# 4_valve_front_connect.net
KiCad netlist of a schematic drawn in EAGLE
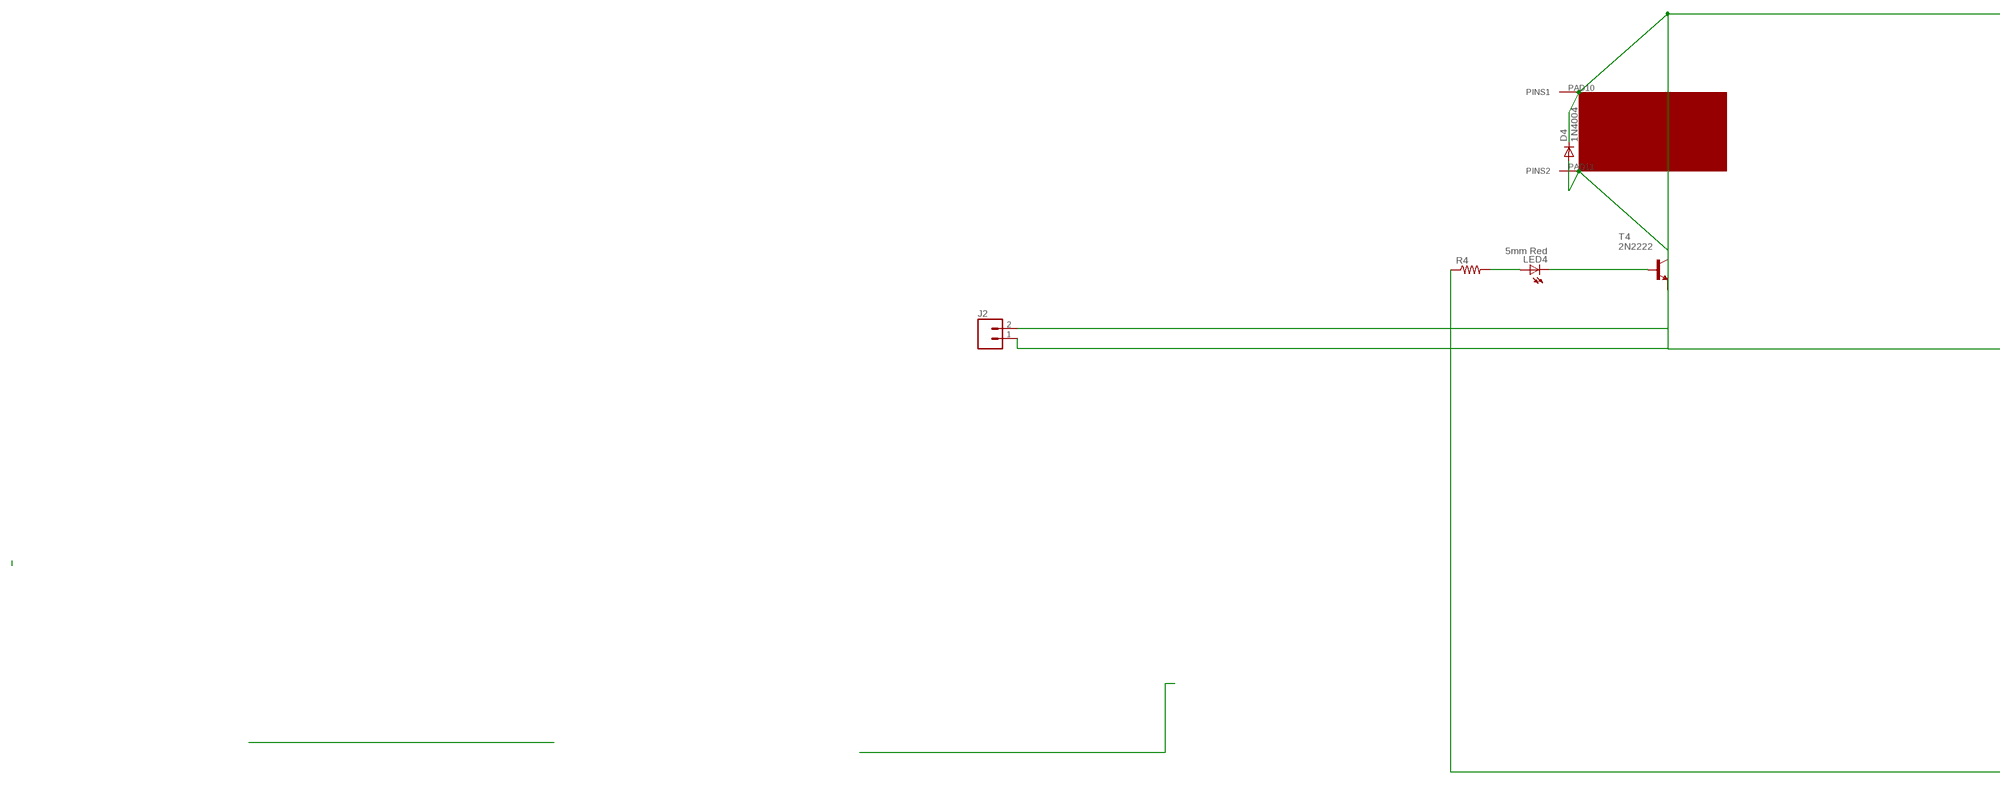
[diagram p0: schematic, sheet 1, part 1 of 2]
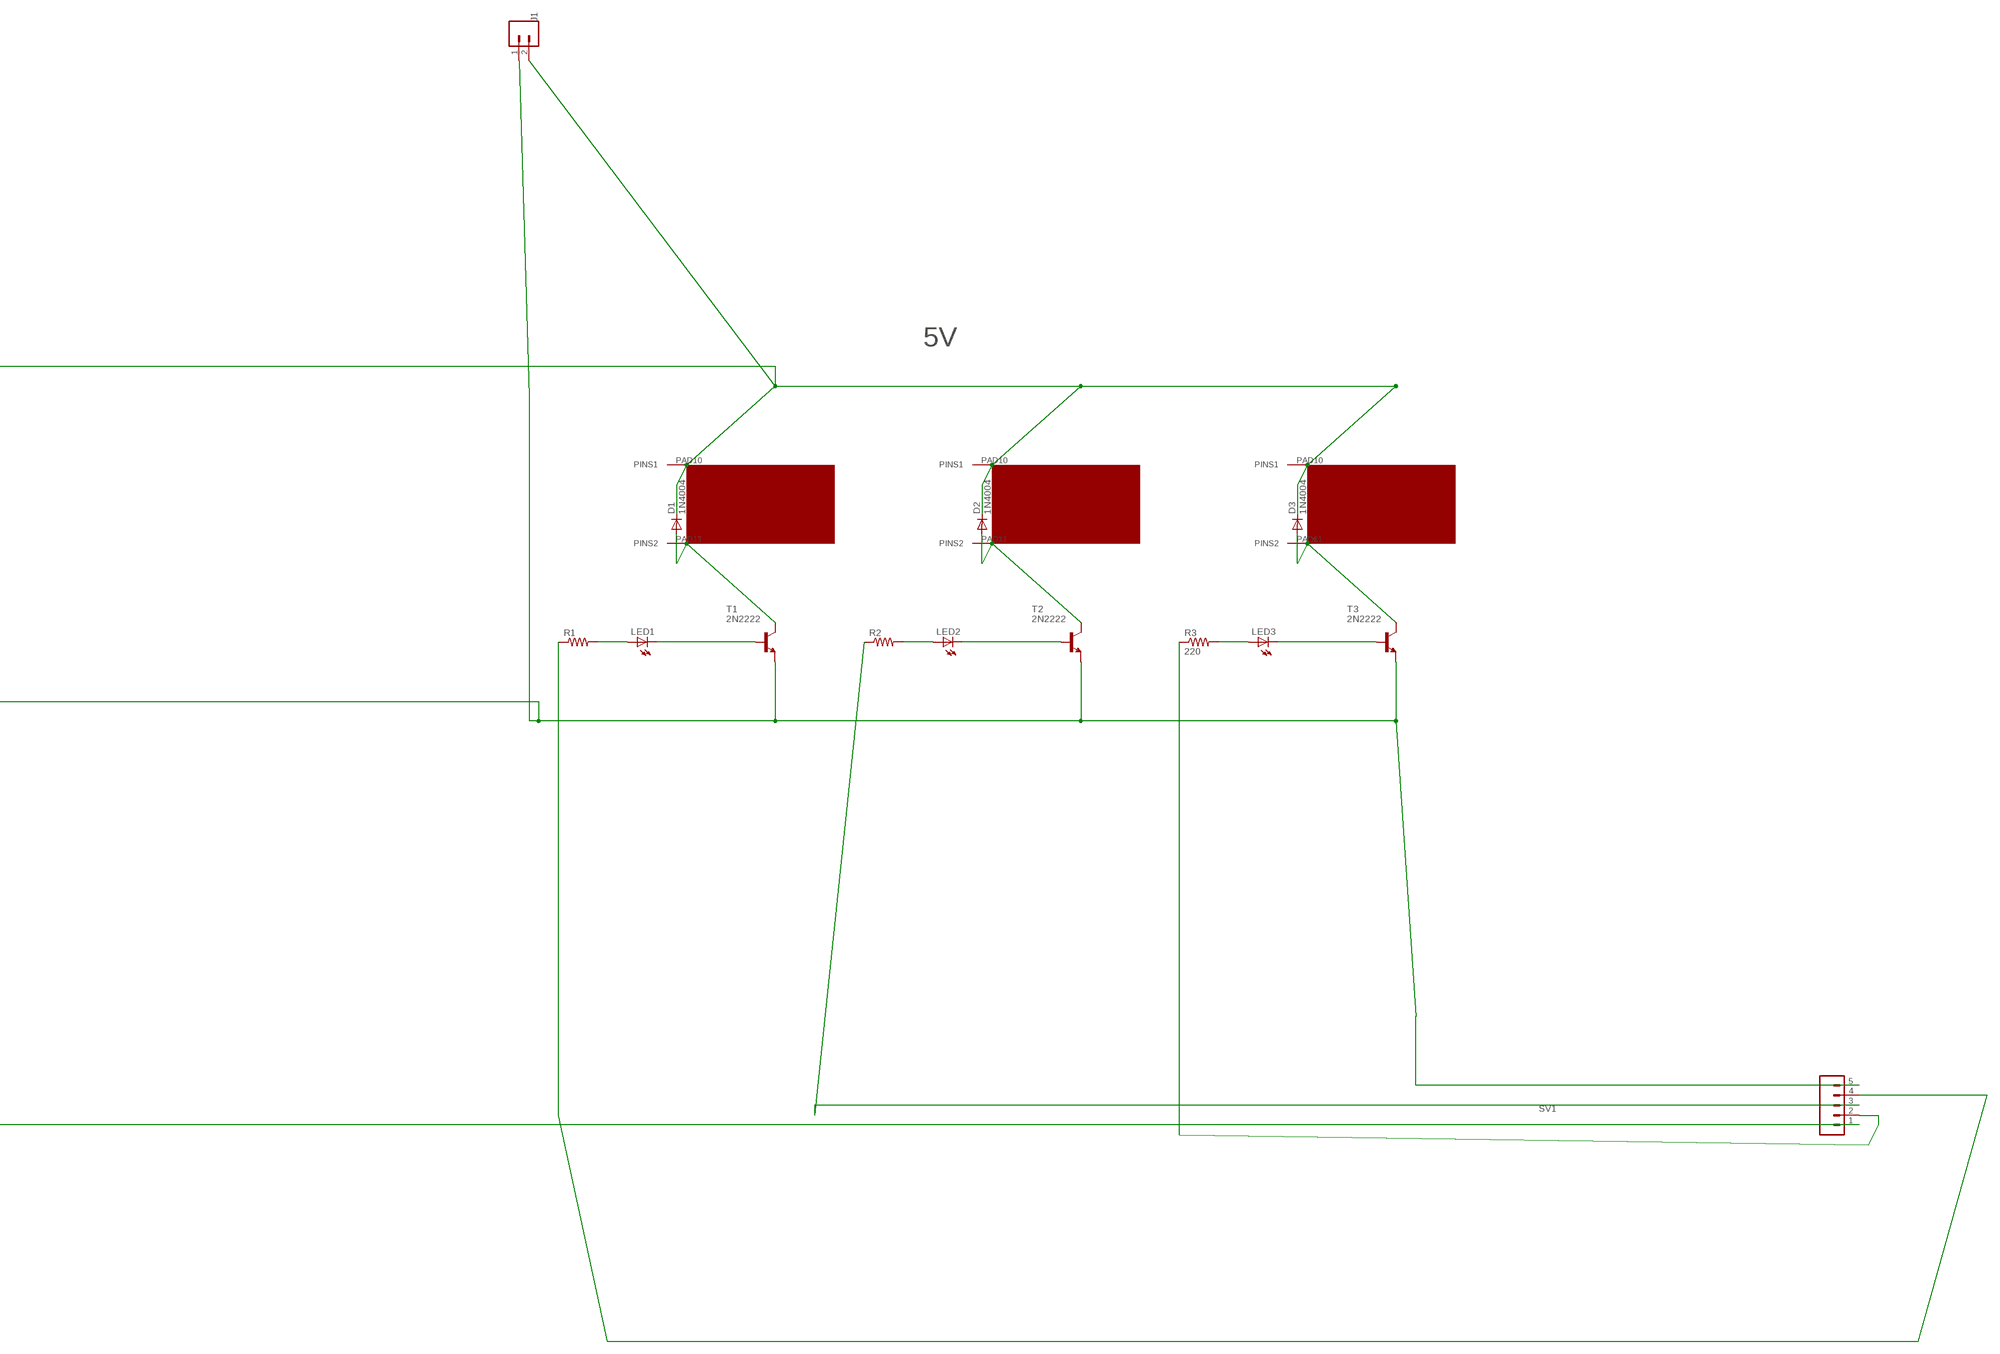
[diagram p1: schematic, sheet 1, part 2 of 2]

(export (version "E")
  (design (tool "Eeschema 10.0.6"))
  (components
    (comp (ref "D1")
      (value "1N4004")
      (footprint "eagle-import:DO41-10")
      (libsource (lib "eagle-import") (part "1N4004"))
    )
    (comp (ref "D2")
      (value "1N4004")
      (footprint "eagle-import:DO41-10")
      (libsource (lib "eagle-import") (part "1N4004"))
    )
    (comp (ref "D3")
      (value "1N4004")
      (footprint "eagle-import:DO41-10")
      (libsource (lib "eagle-import") (part "1N4004"))
    )
    (comp (ref "D4")
      (value "1N4004")
      (footprint "eagle-import:DO41-10")
      (libsource (lib "eagle-import") (part "1N4004"))
    )
    (comp (ref "J1")
      (value "CONN_023.5MM")
      (footprint "eagle-import:SCREWTERMINAL-3.5MM-2")
      (libsource (lib "eagle-import") (part "CONN_023.5MM"))
    )
    (comp (ref "J2")
      (value "CONN_02")
      (footprint "eagle-import:1X02")
      (libsource (lib "eagle-import") (part "CONN_02"))
    )
    (comp (ref "LED1")
      (value "LED5MM")
      (footprint "eagle-import:LED5MM")
      (libsource (lib "eagle-import") (part "LED5MM"))
    )
    (comp (ref "LED2")
      (value "LED5MM")
      (footprint "eagle-import:LED5MM")
      (libsource (lib "eagle-import") (part "LED5MM"))
    )
    (comp (ref "LED3")
      (value "LED5MM")
      (footprint "eagle-import:LED5MM")
      (libsource (lib "eagle-import") (part "LED5MM"))
    )
    (comp (ref "LED4")
      (value "5mm Red")
      (footprint "eagle-import:LED5MM")
      (libsource (lib "eagle-import") (part "LED5MM"))
    )
    (comp (ref "R1")
      (value "R-US_0207/10")
      (footprint "eagle-import:0207_10")
      (libsource (lib "eagle-import") (part "R-US_0207/10"))
    )
    (comp (ref "R2")
      (value "R-US_0207/10")
      (footprint "eagle-import:0207_10")
      (libsource (lib "eagle-import") (part "R-US_0207/10"))
    )
    (comp (ref "R3")
      (value "220")
      (footprint "eagle-import:0207_10")
      (libsource (lib "eagle-import") (part "R-US_0207/10"))
    )
    (comp (ref "R4")
      (value "R-US_0207/10")
      (footprint "eagle-import:0207_10")
      (libsource (lib "eagle-import") (part "R-US_0207/10"))
    )
    (comp (ref "SV1")
      (value "CONN_05")
      (footprint "eagle-import:1X05")
      (libsource (lib "eagle-import") (part "CONN_05"))
    )
    (comp (ref "T1")
      (value "2N2222")
      (footprint "eagle-import:TO92-EBC-OVAL")
      (libsource (lib "eagle-import") (part "2N2222"))
    )
    (comp (ref "T2")
      (value "2N2222")
      (footprint "eagle-import:TO92-EBC-OVAL")
      (libsource (lib "eagle-import") (part "2N2222"))
    )
    (comp (ref "T3")
      (value "2N2222")
      (footprint "eagle-import:TO92-EBC-OVAL")
      (libsource (lib "eagle-import") (part "2N2222"))
    )
    (comp (ref "T4")
      (value "2N2222")
      (footprint "eagle-import:TO92-EBC-OVAL")
      (libsource (lib "eagle-import") (part "2N2222"))
    )
    (comp (ref "U$1")
      (value "VALVE")
      (footprint "eagle-import:VALVTEST2")
      (libsource (lib "eagle-import") (part "VALVE"))
    )
    (comp (ref "U$2")
      (value "VALVE")
      (footprint "eagle-import:VALVTEST2")
      (libsource (lib "eagle-import") (part "VALVE"))
    )
    (comp (ref "U$3")
      (value "VALVE")
      (footprint "eagle-import:VALVTEST2")
      (libsource (lib "eagle-import") (part "VALVE"))
    )
    (comp (ref "VALVE3")
      (value "VALVE")
      (footprint "eagle-import:VALVTEST2")
      (libsource (lib "eagle-import") (part "VALVE"))
    )
  )
  (nets
    (net (code "1") (name "/5V") (class "Default")
      (node (ref "D1") (pin "C") (pinfunction "C_C") (pintype "passive"))
      (node (ref "D2") (pin "C") (pinfunction "C_C") (pintype "passive"))
      (node (ref "D3") (pin "C") (pinfunction "C_C") (pintype "passive"))
      (node (ref "D4") (pin "C") (pinfunction "C_C") (pintype "passive"))
      (node (ref "J1") (pin "2") (pinfunction "2_2") (pintype "passive"))
      (node (ref "J2") (pin "2") (pinfunction "2_2") (pintype "passive"))
      (node (ref "U$1") (pin "PAD10") (pinfunction "PINS1_PAD10") (pintype "bidirectional"))
      (node (ref "U$2") (pin "PAD10") (pinfunction "PINS1_PAD10") (pintype "bidirectional"))
      (node (ref "U$3") (pin "PAD10") (pinfunction "PINS1_PAD10") (pintype "bidirectional"))
      (node (ref "VALVE3") (pin "PAD10") (pinfunction "PINS1_PAD10") (pintype "bidirectional"))
    )
    (net (code "2") (name "Net-(J1-Pad1)") (class "Default")
      (node (ref "J1") (pin "1") (pinfunction "1_1") (pintype "passive"))
      (node (ref "J2") (pin "1") (pinfunction "1_1") (pintype "passive"))
      (node (ref "SV1") (pin "5") (pinfunction "5_5") (pintype "passive"))
      (node (ref "T1") (pin "E") (pinfunction "E_E") (pintype "passive"))
      (node (ref "T2") (pin "E") (pinfunction "E_E") (pintype "passive"))
      (node (ref "T3") (pin "E") (pinfunction "E_E") (pintype "passive"))
      (node (ref "T4") (pin "E") (pinfunction "E_E") (pintype "passive"))
    )
    (net (code "3") (name "Net-(LED1-C)") (class "Default")
      (node (ref "LED1") (pin "K") (pinfunction "C_K") (pintype "passive"))
      (node (ref "T1") (pin "B") (pinfunction "B_B") (pintype "passive"))
    )
    (net (code "4") (name "Net-(LED1-PadA)") (class "Default")
      (node (ref "LED1") (pin "A") (pinfunction "A_A") (pintype "passive"))
      (node (ref "R1") (pin "2") (pinfunction "2_2") (pintype "passive"))
    )
    (net (code "5") (name "Net-(LED2-C)") (class "Default")
      (node (ref "LED2") (pin "K") (pinfunction "C_K") (pintype "passive"))
      (node (ref "T2") (pin "B") (pinfunction "B_B") (pintype "passive"))
    )
    (net (code "6") (name "Net-(LED2-PadA)") (class "Default")
      (node (ref "LED2") (pin "A") (pinfunction "A_A") (pintype "passive"))
      (node (ref "R2") (pin "2") (pinfunction "2_2") (pintype "passive"))
    )
    (net (code "7") (name "Net-(LED3-C)") (class "Default")
      (node (ref "LED3") (pin "K") (pinfunction "C_K") (pintype "passive"))
      (node (ref "T3") (pin "B") (pinfunction "B_B") (pintype "passive"))
    )
    (net (code "8") (name "Net-(LED3-PadA)") (class "Default")
      (node (ref "LED3") (pin "A") (pinfunction "A_A") (pintype "passive"))
      (node (ref "R3") (pin "2") (pinfunction "2_2") (pintype "passive"))
    )
    (net (code "9") (name "Net-(LED4-C)") (class "Default")
      (node (ref "LED4") (pin "K") (pinfunction "C_K") (pintype "passive"))
      (node (ref "T4") (pin "B") (pinfunction "B_B") (pintype "passive"))
    )
    (net (code "10") (name "Net-(LED4-PadA)") (class "Default")
      (node (ref "LED4") (pin "A") (pinfunction "A_A") (pintype "passive"))
      (node (ref "R4") (pin "2") (pinfunction "2_2") (pintype "passive"))
    )
    (net (code "11") (name "Net-(R1-Pad1)") (class "Default")
      (node (ref "R1") (pin "1") (pinfunction "1_1") (pintype "passive"))
      (node (ref "SV1") (pin "4") (pinfunction "4_4") (pintype "passive"))
    )
    (net (code "12") (name "Net-(R2-Pad1)") (class "Default")
      (node (ref "R2") (pin "1") (pinfunction "1_1") (pintype "passive"))
      (node (ref "SV1") (pin "3") (pinfunction "3_3") (pintype "passive"))
    )
    (net (code "13") (name "Net-(R3-Pad1)") (class "Default")
      (node (ref "R3") (pin "1") (pinfunction "1_1") (pintype "passive"))
      (node (ref "SV1") (pin "2") (pinfunction "2_2") (pintype "passive"))
    )
    (net (code "14") (name "Net-(R4-Pad1)") (class "Default")
      (node (ref "R4") (pin "1") (pinfunction "1_1") (pintype "passive"))
      (node (ref "SV1") (pin "1") (pinfunction "1_1") (pintype "passive"))
    )
    (net (code "15") (name "Net-(U$1-PINS2)") (class "Default")
      (node (ref "D1") (pin "A") (pinfunction "A_A") (pintype "passive"))
      (node (ref "T1") (pin "C") (pinfunction "C_C") (pintype "passive"))
      (node (ref "U$1") (pin "PAD11") (pinfunction "PINS2_PAD11") (pintype "bidirectional"))
    )
    (net (code "16") (name "Net-(U$2-PINS2)") (class "Default")
      (node (ref "D2") (pin "A") (pinfunction "A_A") (pintype "passive"))
      (node (ref "T2") (pin "C") (pinfunction "C_C") (pintype "passive"))
      (node (ref "U$2") (pin "PAD11") (pinfunction "PINS2_PAD11") (pintype "bidirectional"))
    )
    (net (code "17") (name "Net-(U$3-PINS2)") (class "Default")
      (node (ref "D4") (pin "A") (pinfunction "A_A") (pintype "passive"))
      (node (ref "T4") (pin "C") (pinfunction "C_C") (pintype "passive"))
      (node (ref "U$3") (pin "PAD11") (pinfunction "PINS2_PAD11") (pintype "bidirectional"))
    )
    (net (code "18") (name "Net-(VALVE3-PINS2)") (class "Default")
      (node (ref "D3") (pin "A") (pinfunction "A_A") (pintype "passive"))
      (node (ref "T3") (pin "C") (pinfunction "C_C") (pintype "passive"))
      (node (ref "VALVE3") (pin "PAD11") (pinfunction "PINS2_PAD11") (pintype "bidirectional"))
    )
  )
)
